# Back-end_2.net
KiCad netlist of a schematic drawn in Altium Designer
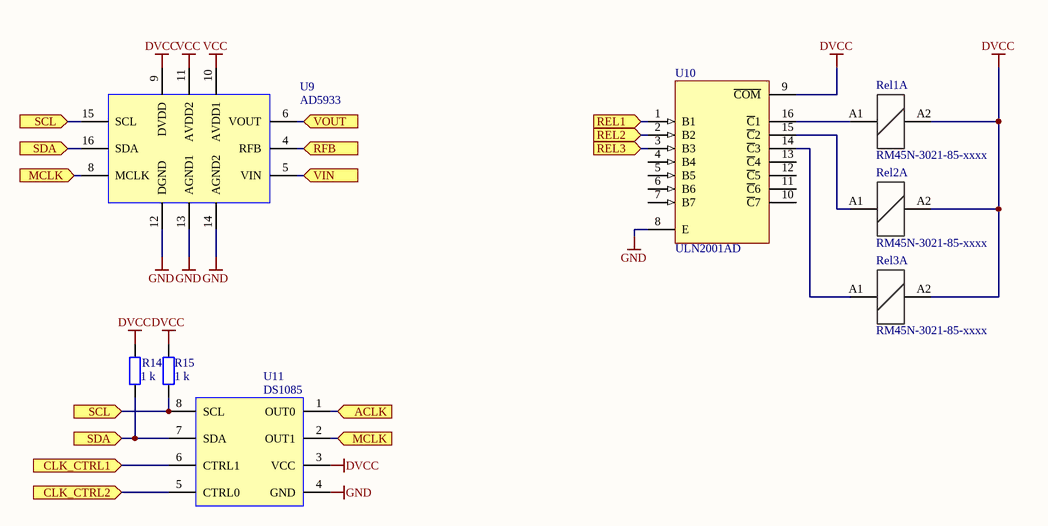
[diagram p0: Back-end_2.SchDoc]

(export (version "E")
  (design (tool "Eeschema 10.0.6"))
  (components
    (comp (ref "R14")
      (value "1 k")
      (footprint "R1206")
      (description "Resistor")
      (fields (field (name "PUBLISHER") "Altium Limited"))
      (libsource (lib "Miscellaneous Devices") (part "Res2"))
    )
    (comp (ref "R15")
      (value "1 k")
      (footprint "R1206")
      (description "Resistor")
      (fields (field (name "PUBLISHER") "Altium Limited"))
      (libsource (lib "Miscellaneous Devices") (part "Res2"))
    )
    (comp (ref "Rel1") (value "RM45N-3021-85-xxxx") (libsource (lib "Schlib1") (part "RM45N-3021-85-xxxx")))
    (comp (ref "Rel2") (value "RM45N-3021-85-xxxx") (libsource (lib "Schlib1") (part "RM45N-3021-85-xxxx")))
    (comp (ref "Rel3") (value "RM45N-3021-85-xxxx") (libsource (lib "Schlib1") (part "RM45N-3021-85-xxxx")))
    (comp (ref "U9") (value "AD5933") (libsource (lib "Schlib1") (part "AD5933")))
    (comp (ref "U10")
      (value "ULN2001AD")
      (footprint "D016_N")
      (description "Darlington Transistor Array")
      (fields (field (name "PUBLISHER") "Altium Limited"))
      (libsource (lib "TI Interface Darlington Driver") (part "ULN2001AD"))
    )
    (comp (ref "U11") (value "DS1085") (libsource (lib "Schlib1") (part "DS1085")))
  )
  (nets
    (net (code "1") (name "/ACLK") (class "Default")
      (node (ref "U11") (pin "1") (pinfunction "OUT0_1") (pintype "passive"))
    )
    (net (code "2") (name "/CLK_CTRL1") (class "Default")
      (node (ref "U11") (pin "6") (pinfunction "CTRL1_6") (pintype "passive"))
    )
    (net (code "3") (name "/CLK_CTRL2") (class "Default")
      (node (ref "U11") (pin "5") (pinfunction "CTRL0_5") (pintype "passive"))
    )
    (net (code "4") (name "/MCLK") (class "Default")
      (node (ref "U11") (pin "2") (pinfunction "OUT1_2") (pintype "passive"))
      (node (ref "U9") (pin "8") (pinfunction "MCLK_8") (pintype "passive"))
    )
    (net (code "5") (name "/REL1") (class "Default")
      (node (ref "U10") (pin "1") (pinfunction "B1_1") (pintype "input"))
    )
    (net (code "6") (name "/REL2") (class "Default")
      (node (ref "U10") (pin "2") (pinfunction "B2_2") (pintype "input"))
    )
    (net (code "7") (name "/REL3") (class "Default")
      (node (ref "U10") (pin "3") (pinfunction "B3_3") (pintype "input"))
    )
    (net (code "8") (name "/RFB") (class "Default")
      (node (ref "U9") (pin "4") (pinfunction "RFB_4") (pintype "passive"))
    )
    (net (code "9") (name "/SCL") (class "Default")
      (node (ref "R15") (pin "1") (pinfunction "1_1") (pintype "passive"))
      (node (ref "U11") (pin "8") (pinfunction "SCL_8") (pintype "passive"))
      (node (ref "U9") (pin "15") (pinfunction "SCL_15") (pintype "passive"))
    )
    (net (code "10") (name "/SDA") (class "Default")
      (node (ref "R14") (pin "1") (pinfunction "1_1") (pintype "passive"))
      (node (ref "U11") (pin "7") (pinfunction "SDA_7") (pintype "passive"))
      (node (ref "U9") (pin "16") (pinfunction "SDA_16") (pintype "passive"))
    )
    (net (code "11") (name "/VIN") (class "Default")
      (node (ref "U9") (pin "5") (pinfunction "VIN_5") (pintype "passive"))
    )
    (net (code "12") (name "/VOUT") (class "Default")
      (node (ref "U9") (pin "6") (pinfunction "VOUT_6") (pintype "passive"))
    )
    (net (code "13") (name "DVCC") (class "Default")
      (node (ref "R14") (pin "2") (pinfunction "2_2") (pintype "passive"))
      (node (ref "R15") (pin "2") (pinfunction "2_2") (pintype "passive"))
      (node (ref "Rel1") (pin "A2") (pinfunction "COIL_A2") (pintype "passive"))
      (node (ref "Rel2") (pin "A2") (pinfunction "COIL_A2") (pintype "passive"))
      (node (ref "Rel3") (pin "A2") (pinfunction "COIL_A2") (pintype "passive"))
      (node (ref "U10") (pin "9") (pinfunction "~{COM}_9") (pintype "passive"))
      (node (ref "U11") (pin "3") (pinfunction "VCC_3") (pintype "passive"))
      (node (ref "U9") (pin "9") (pinfunction "DVDD_9") (pintype "passive"))
    )
    (net (code "14") (name "GND") (class "Default")
      (node (ref "U10") (pin "8") (pinfunction "E_8") (pintype "power_in"))
      (node (ref "U11") (pin "4") (pinfunction "GND_4") (pintype "passive"))
      (node (ref "U9") (pin "12") (pinfunction "DGND_12") (pintype "passive"))
      (node (ref "U9") (pin "13") (pinfunction "AGND1_13") (pintype "passive"))
      (node (ref "U9") (pin "14") (pinfunction "AGND2_14") (pintype "passive"))
    )
    (net (code "15") (name "Net-(U10-~{C}1)") (class "Default")
      (node (ref "Rel1") (pin "A1") (pinfunction "COIL_A1") (pintype "passive"))
      (node (ref "U10") (pin "16") (pinfunction "~{C}1_16") (pintype "open_collector"))
    )
    (net (code "16") (name "Net-(U10-~{C}2)") (class "Default")
      (node (ref "Rel2") (pin "A1") (pinfunction "COIL_A1") (pintype "passive"))
      (node (ref "U10") (pin "15") (pinfunction "~{C}2_15") (pintype "open_collector"))
    )
    (net (code "17") (name "Net-(U10-~{C}3)") (class "Default")
      (node (ref "Rel3") (pin "A1") (pinfunction "COIL_A1") (pintype "passive"))
      (node (ref "U10") (pin "14") (pinfunction "~{C}3_14") (pintype "open_collector"))
    )
    (net (code "18") (name "VCC") (class "Default")
      (node (ref "U9") (pin "10") (pinfunction "AVDD1_10") (pintype "passive"))
      (node (ref "U9") (pin "11") (pinfunction "AVDD2_11") (pintype "passive"))
    )
    (net (code "19") (name "unconnected-(U10-B4-Pad4)") (class "Default")
      (node (ref "U10") (pin "4") (pinfunction "B4_4") (pintype "input"))
    )
    (net (code "20") (name "unconnected-(U10-B5-Pad5)") (class "Default")
      (node (ref "U10") (pin "5") (pinfunction "B5_5") (pintype "input"))
    )
    (net (code "21") (name "unconnected-(U10-B6-Pad6)") (class "Default")
      (node (ref "U10") (pin "6") (pinfunction "B6_6") (pintype "input"))
    )
    (net (code "22") (name "unconnected-(U10-B7-Pad7)") (class "Default")
      (node (ref "U10") (pin "7") (pinfunction "B7_7") (pintype "input"))
    )
    (net (code "23") (name "unconnected-(U10-~{C}4-Pad13)") (class "Default")
      (node (ref "U10") (pin "13") (pinfunction "~{C}4_13") (pintype "open_collector"))
    )
    (net (code "24") (name "unconnected-(U10-~{C}5-Pad12)") (class "Default")
      (node (ref "U10") (pin "12") (pinfunction "~{C}5_12") (pintype "open_collector"))
    )
    (net (code "25") (name "unconnected-(U10-~{C}6-Pad11)") (class "Default")
      (node (ref "U10") (pin "11") (pinfunction "~{C}6_11") (pintype "open_collector"))
    )
    (net (code "26") (name "unconnected-(U10-~{C}7-Pad10)") (class "Default")
      (node (ref "U10") (pin "10") (pinfunction "~{C}7_10") (pintype "open_collector"))
    )
  )
)
